# WZ4827R043-ESP32-V1_1-20230322.net
KiCad netlist of a schematic drawn in EAGLE
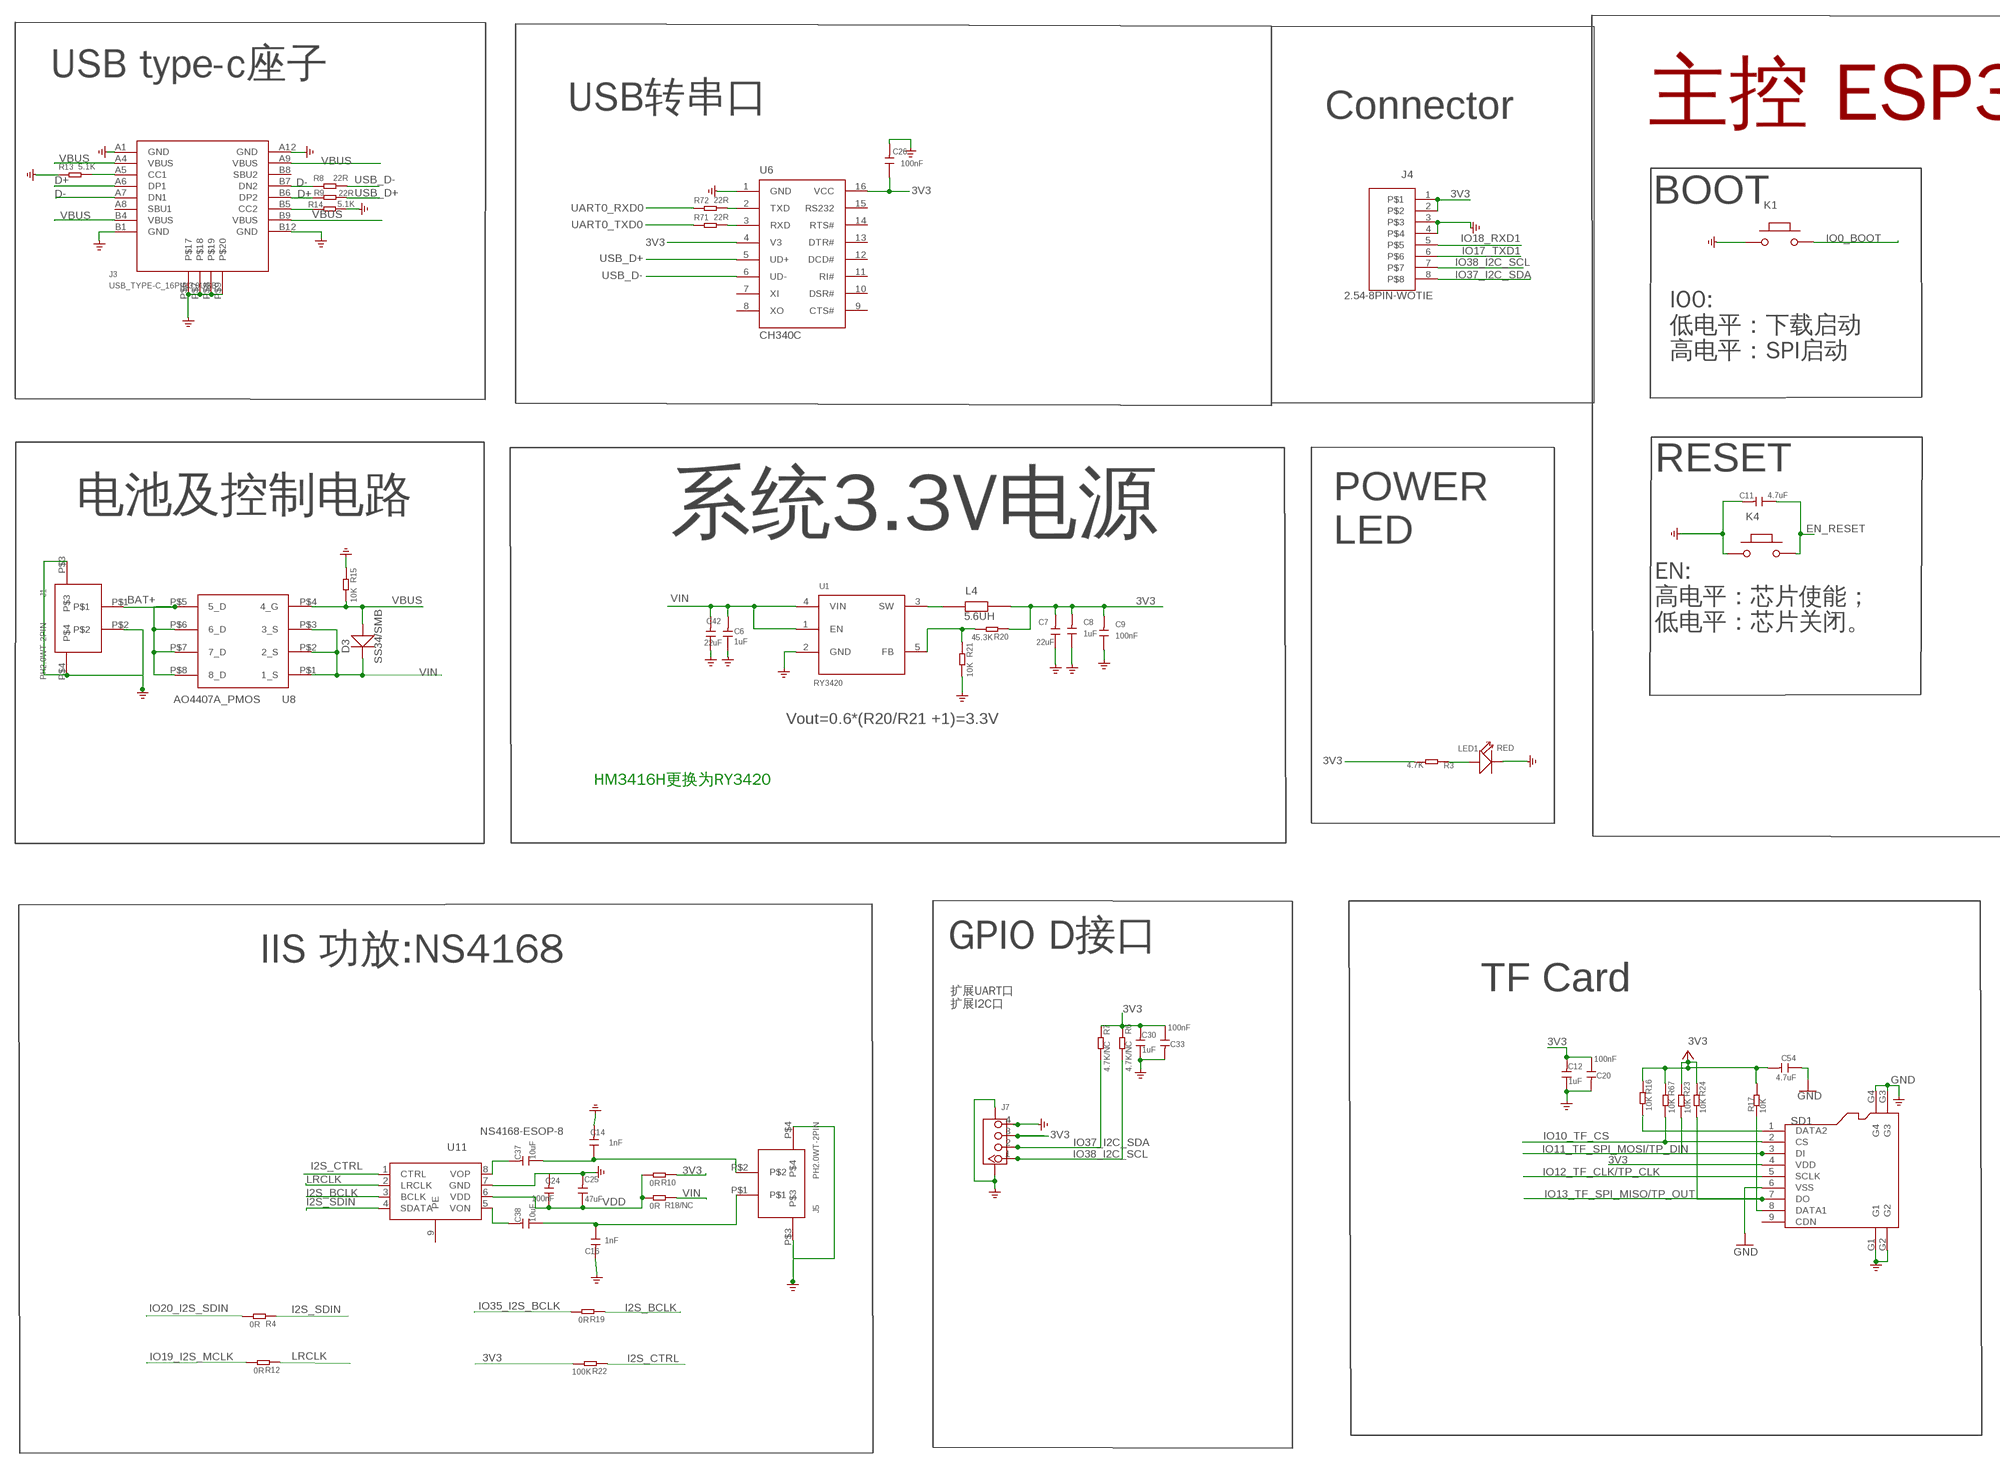
[diagram p0: schematic, sheet 1, part 1 of 2]
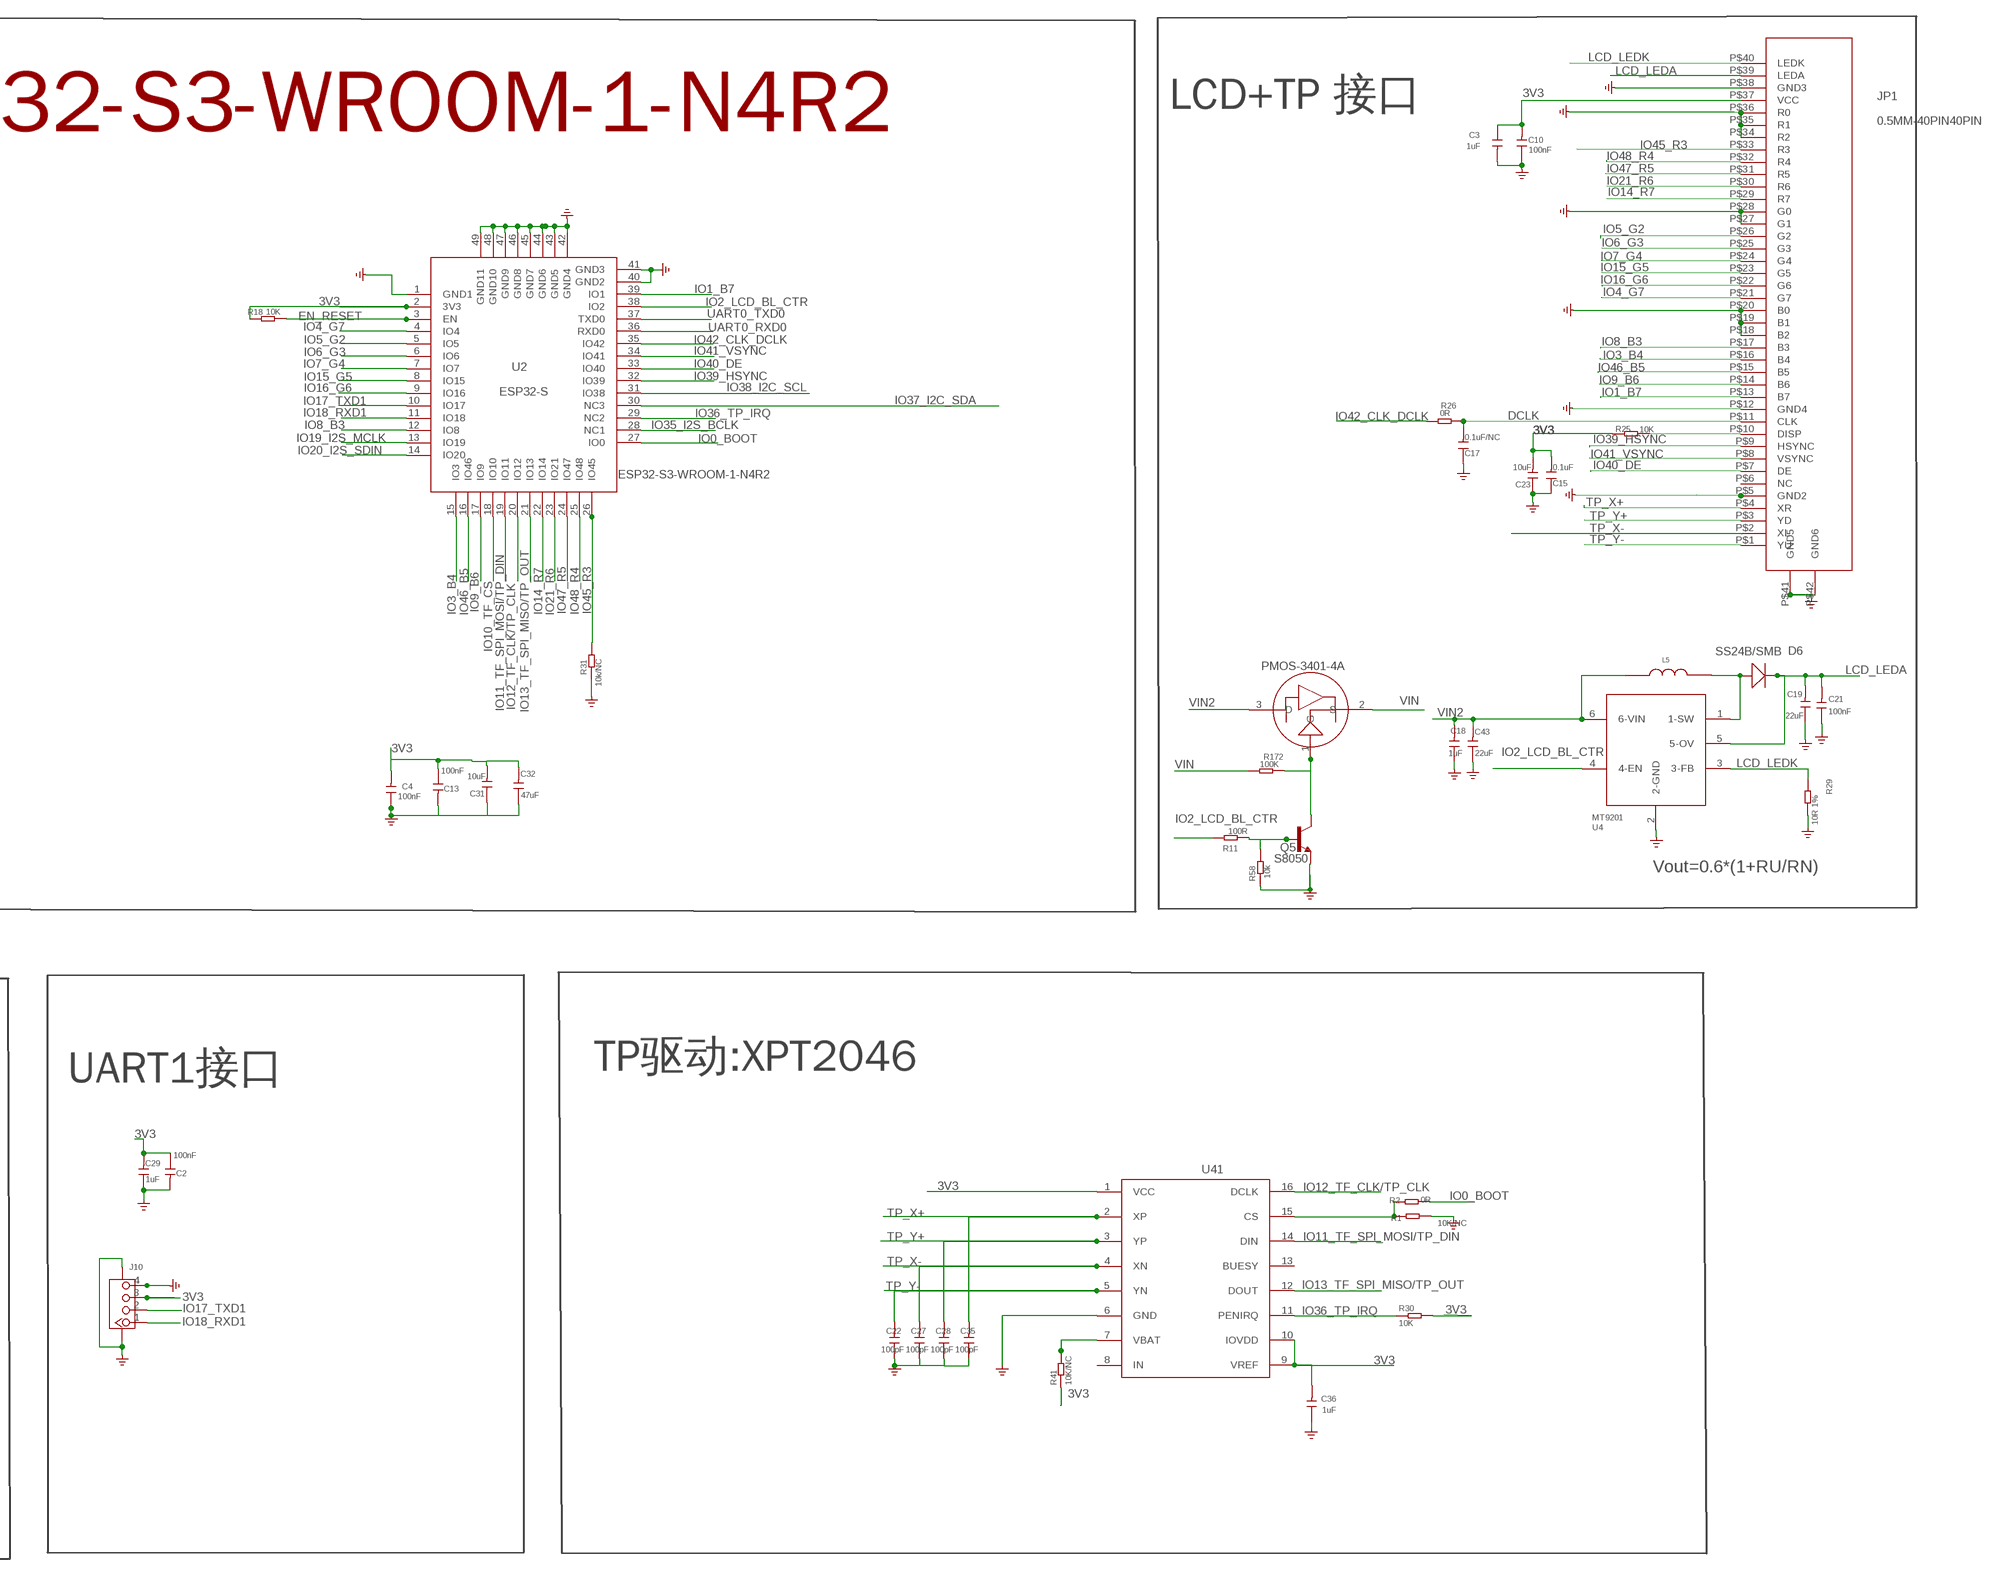
[diagram p1: schematic, sheet 1, part 2 of 2]

(export (version "E")
  (design (tool "Eeschema 10.0.6"))
  (components
    (comp (ref "C2")
      (value "100nF")
      (footprint "eagle-import:C0603")
      (libsource (lib "eagle-import") (part "C-0603"))
    )
    (comp (ref "C3")
      (value "1uF")
      (footprint "eagle-import:C0603")
      (libsource (lib "eagle-import") (part "C-0603"))
    )
    (comp (ref "C4")
      (value "100nF")
      (footprint "eagle-import:C0603")
      (libsource (lib "eagle-import") (part "C-0603"))
    )
    (comp (ref "C6")
      (value "1uF")
      (footprint "eagle-import:0603")
      (libsource (lib "eagle-import") (part "C0603"))
    )
    (comp (ref "C7")
      (value "22uF")
      (footprint "eagle-import:0805")
      (libsource (lib "eagle-import") (part "C0805"))
    )
    (comp (ref "C8")
      (value "1uF")
      (footprint "eagle-import:0603")
      (libsource (lib "eagle-import") (part "C0603"))
    )
    (comp (ref "C9")
      (value "100nF")
      (footprint "eagle-import:0603")
      (libsource (lib "eagle-import") (part "C0603"))
    )
    (comp (ref "C10")
      (value "100nF")
      (footprint "eagle-import:C0603")
      (libsource (lib "eagle-import") (part "C-0603"))
    )
    (comp (ref "C11")
      (value "4.7uF")
      (footprint "eagle-import:0603")
      (libsource (lib "eagle-import") (part "C0603"))
    )
    (comp (ref "C12")
      (value "1uF")
      (footprint "eagle-import:DISCRETE_C0603")
      (libsource (lib "eagle-import") (part "A_xbj_DISCRETE_C-0603"))
    )
    (comp (ref "C13")
      (value "100nF")
      (footprint "eagle-import:C0603")
      (libsource (lib "eagle-import") (part "C-0603"))
    )
    (comp (ref "C14")
      (value "1nF")
      (footprint "eagle-import:C0603")
      (libsource (lib "eagle-import") (part "C-0603"))
    )
    (comp (ref "C15")
      (value "0.1uF")
      (footprint "eagle-import:DISCRETE_C0603")
      (libsource (lib "eagle-import") (part "DISCRETE_C-0603"))
    )
    (comp (ref "C16")
      (value "1nF")
      (footprint "eagle-import:C0603")
      (libsource (lib "eagle-import") (part "C-0603"))
    )
    (comp (ref "C17")
      (value "0.1uF/NC")
      (footprint "eagle-import:DISCRETE_C0603")
      (libsource (lib "eagle-import") (part "DISCRETE_C-0603"))
    )
    (comp (ref "C18")
      (value "1uF")
      (footprint "eagle-import:0603")
      (libsource (lib "eagle-import") (part "C0603"))
    )
    (comp (ref "C19")
      (value "22uF")
      (footprint "eagle-import:0805")
      (libsource (lib "eagle-import") (part "C0805"))
    )
    (comp (ref "C20")
      (value "100nF")
      (footprint "eagle-import:C0603")
      (libsource (lib "eagle-import") (part "C-0603"))
    )
    (comp (ref "C21")
      (value "100nF")
      (footprint "eagle-import:0603")
      (libsource (lib "eagle-import") (part "C0603"))
    )
    (comp (ref "C22")
      (value "100pF")
      (footprint "eagle-import:0603")
      (libsource (lib "eagle-import") (part "C0603"))
    )
    (comp (ref "C23")
      (value "10uF")
      (footprint "eagle-import:DISCRETE_C0603")
      (libsource (lib "eagle-import") (part "DISCRETE_C-0603"))
    )
    (comp (ref "C24")
      (value "100nF")
      (footprint "eagle-import:C0603")
      (libsource (lib "eagle-import") (part "C-0603"))
    )
    (comp (ref "C25")
      (value "47uF")
      (footprint "eagle-import:0805")
      (libsource (lib "eagle-import") (part "C0805"))
    )
    (comp (ref "C26")
      (value "100nF")
      (footprint "eagle-import:0603")
      (libsource (lib "eagle-import") (part "C0603"))
    )
    (comp (ref "C27")
      (value "100pF")
      (footprint "eagle-import:0603")
      (libsource (lib "eagle-import") (part "C0603"))
    )
    (comp (ref "C28")
      (value "100pF")
      (footprint "eagle-import:0603")
      (libsource (lib "eagle-import") (part "C0603"))
    )
    (comp (ref "C29")
      (value "1uF")
      (footprint "eagle-import:DISCRETE_C0603")
      (libsource (lib "eagle-import") (part "A_xbj_DISCRETE_C-0603"))
    )
    (comp (ref "C30")
      (value "1uF")
      (footprint "eagle-import:DISCRETE_C0603")
      (libsource (lib "eagle-import") (part "A_xbj_DISCRETE_C-0603"))
    )
    (comp (ref "C31")
      (value "10uF")
      (footprint "eagle-import:DISCRETE_C0603")
      (libsource (lib "eagle-import") (part "DISCRETE_C-0603"))
    )
    (comp (ref "C32")
      (value "47uF")
      (footprint "eagle-import:0805")
      (libsource (lib "eagle-import") (part "C0805"))
    )
    (comp (ref "C33")
      (value "100nF")
      (footprint "eagle-import:C0603")
      (libsource (lib "eagle-import") (part "C-0603"))
    )
    (comp (ref "C35")
      (value "100pF")
      (footprint "eagle-import:0603")
      (libsource (lib "eagle-import") (part "C0603"))
    )
    (comp (ref "C36")
      (value "1uF")
      (footprint "eagle-import:DISCRETE_C0603")
      (libsource (lib "eagle-import") (part "A_xbj_DISCRETE_C-0603"))
    )
    (comp (ref "C37")
      (value "10uF")
      (footprint "eagle-import:DISCRETE_C0603")
      (libsource (lib "eagle-import") (part "A_xbj_DISCRETE_C-0603"))
    )
    (comp (ref "C38")
      (value "10uF")
      (footprint "eagle-import:DISCRETE_C0603")
      (libsource (lib "eagle-import") (part "A_xbj_DISCRETE_C-0603"))
    )
    (comp (ref "C42")
      (value "22uF")
      (footprint "eagle-import:0805")
      (libsource (lib "eagle-import") (part "C0805"))
    )
    (comp (ref "C43")
      (value "22uF")
      (footprint "eagle-import:0805")
      (libsource (lib "eagle-import") (part "C0805"))
    )
    (comp (ref "C54")
      (value "4.7uF")
      (footprint "eagle-import:DISCRETE_C0603")
      (libsource (lib "eagle-import") (part "DISCRETE_C-0603"))
    )
    (comp (ref "D3")
      (value "SS34/SMB")
      (footprint "eagle-import:214AB")
      (libsource (lib "eagle-import") (part "214ABDO-214AB"))
    )
    (comp (ref "D6")
      (value "SS24B/SMB")
      (footprint "eagle-import:214AB")
      (libsource (lib "eagle-import") (part "214ABDO-214AB"))
    )
    (comp (ref "J1")
      (value "PH2.0WT-2PIN")
      (footprint "eagle-import:PH2.0WT-2PIN")
      (libsource (lib "eagle-import") (part "PH2.0WT-2PIN"))
    )
    (comp (ref "J3")
      (value "USB_TYPE-C_16PIN3.0USB")
      (footprint "eagle-import:KEVIN_3.0TYPEC-SMD")
      (libsource (lib "eagle-import") (part "USB_TYPE-C_16PIN3.0USB"))
    )
    (comp (ref "J4")
      (value "2.54-8PIN-WOTIE")
      (footprint "eagle-import:2.54-8P-WOTIE")
      (libsource (lib "eagle-import") (part "2.54-8PIN-WOTIE"))
    )
    (comp (ref "J5")
      (value "PH2.0WT-2PIN")
      (footprint "eagle-import:PH2.0WT-2PIN")
      (libsource (lib "eagle-import") (part "PH2.0WT-2PIN"))
    )
    (comp (ref "J7")
      (value "CONNECTOR_TWIG-4P-2.0-SMD-FEMALE-REINFORCE90D")
      (footprint "eagle-import:CONNECTOR_4P-SMD-2.0-90D")
      (libsource (lib "eagle-import") (part "CONNECTOR_TWIG-4P-2.0-SMD-FEMALE-REINFORCE90D"))
    )
    (comp (ref "J10")
      (value "CONNECTOR_TWIG-4P-2.0-SMD-FEMALE-REINFORCE90D")
      (footprint "eagle-import:CONNECTOR_4P-SMD-2.0-90D")
      (libsource (lib "eagle-import") (part "CONNECTOR_TWIG-4P-2.0-SMD-FEMALE-REINFORCE90D"))
    )
    (comp (ref "JP1")
      (value "0.5MM-40PIN40PIN")
      (footprint "eagle-import:0.5MM_40P")
      (libsource (lib "eagle-import") (part "0.5MM-40PIN40PIN"))
    )
    (comp (ref "K1")
      (value "BUTTON")
      (footprint "eagle-import:157SW")
      (libsource (lib "eagle-import") (part "PB157"))
    )
    (comp (ref "K4")
      (value "BUTTON")
      (footprint "eagle-import:157SW")
      (libsource (lib "eagle-import") (part "PB157"))
    )
    (comp (ref "L4")
      (value "5.6UH")
      (footprint "eagle-import:CD54")
      (libsource (lib "eagle-import") (part "CROWPI2-MB-V1.4-20211012_CMP201209UD1R0MT"))
    )
    (comp (ref "L5")
      (value "CD32_6.8uH")
      (footprint "eagle-import:CD32")
      (libsource (lib "eagle-import") (part "CD32_950MA"))
    )
    (comp (ref "LED1")
      (value "RED")
      (footprint "eagle-import:DISCRETE_LED-0603")
      (libsource (lib "eagle-import") (part "DISCRETE_LED0603"))
    )
    (comp (ref "Q5")
      (value "S8050")
      (footprint "eagle-import:SPARKFUN_SOT23")
      (libsource (lib "eagle-import") (part "SPARKFUN_TRANSISTOR_NPNSOT23"))
    )
    (comp (ref "Q30")
      (value "PMOS-3401-4A")
      (footprint "eagle-import:SOT-23")
      (libsource (lib "eagle-import") (part "P-MOS-SOT23"))
    )
    (comp (ref "R1")
      (value "10K/NC")
      (footprint "eagle-import:R0603")
      (libsource (lib "eagle-import") (part "R0603"))
    )
    (comp (ref "R2")
      (value "0R")
      (footprint "eagle-import:DISCRETE_R0603")
      (libsource (lib "eagle-import") (part "Crowtail-_LED-V2.0-20190615-01_DISCRETE_R-0603"))
    )
    (comp (ref "R3")
      (value "4.7K")
      (footprint "eagle-import:DISCRETE_R0603")
      (libsource (lib "eagle-import") (part "Crowtail-_LED-V2.0-20190615-01_DISCRETE_R-0603"))
    )
    (comp (ref "R4")
      (value "0R")
      (footprint "eagle-import:DISCRETE_R0603")
      (libsource (lib "eagle-import") (part "Crowtail-_LED-V2.0-20190615-01_DISCRETE_R-0603"))
    )
    (comp (ref "R6")
      (value "4.7K/NC")
      (footprint "eagle-import:DISCRETE_R0603")
      (libsource (lib "eagle-import") (part "Crowtail-_LED-V2.0-20190615-01_DISCRETE_R-0603"))
    )
    (comp (ref "R7")
      (value "4.7K/NC")
      (footprint "eagle-import:DISCRETE_R0603")
      (libsource (lib "eagle-import") (part "Crowtail-_LED-V2.0-20190615-01_DISCRETE_R-0603"))
    )
    (comp (ref "R8")
      (value "22R")
      (footprint "eagle-import:DISCRETE_R0603")
      (libsource (lib "eagle-import") (part "Crowtail-_LED-V2.0-20190615-01_DISCRETE_R-0603"))
    )
    (comp (ref "R9")
      (value "22R")
      (footprint "eagle-import:DISCRETE_R0603")
      (libsource (lib "eagle-import") (part "Crowtail-_LED-V2.0-20190615-01_DISCRETE_R-0603"))
    )
    (comp (ref "R10")
      (value "0R")
      (footprint "eagle-import:DISCRETE_R0603")
      (libsource (lib "eagle-import") (part "Crowtail-_LED-V2.0-20190615-01_DISCRETE_R-0603"))
    )
    (comp (ref "R11")
      (value "100R")
      (footprint "eagle-import:R0603")
      (libsource (lib "eagle-import") (part "R0603"))
    )
    (comp (ref "R12")
      (value "0R")
      (footprint "eagle-import:DISCRETE_R0603")
      (libsource (lib "eagle-import") (part "Crowtail-_LED-V2.0-20190615-01_DISCRETE_R-0603"))
    )
    (comp (ref "R13")
      (value "5.1K")
      (footprint "eagle-import:DISCRETE_R0603")
      (libsource (lib "eagle-import") (part "Crowtail-_LED-V2.0-20190615-01_DISCRETE_R-0603"))
    )
    (comp (ref "R14")
      (value "5.1K")
      (footprint "eagle-import:DISCRETE_R0603")
      (libsource (lib "eagle-import") (part "Crowtail-_LED-V2.0-20190615-01_DISCRETE_R-0603"))
    )
    (comp (ref "R15")
      (value "10K")
      (footprint "eagle-import:DISCRETE_R0603")
      (libsource (lib "eagle-import") (part "Crowtail-_LED-V2.0-20190615-01_DISCRETE_R-0603"))
    )
    (comp (ref "R16")
      (value "10K")
      (footprint "eagle-import:DISCRETE_R0603")
      (libsource (lib "eagle-import") (part "Crowtail-_LED-V2.0-20190615-01_DISCRETE_R-0603"))
    )
    (comp (ref "R17")
      (value "10K")
      (footprint "eagle-import:DISCRETE_R0603")
      (libsource (lib "eagle-import") (part "Crowtail-_LED-V2.0-20190615-01_DISCRETE_R-0603"))
    )
    (comp (ref "R18")
      (value "10K")
      (footprint "eagle-import:DISCRETE_R0603")
      (libsource (lib "eagle-import") (part "Crowtail-_LED-V2.0-20190615-01_DISCRETE_R-0603"))
    )
    (comp (ref "R18/NC")
      (value "0R")
      (footprint "eagle-import:DISCRETE_R0603")
      (libsource (lib "eagle-import") (part "Crowtail-_LED-V2.0-20190615-01_DISCRETE_R-0603"))
    )
    (comp (ref "R19")
      (value "0R")
      (footprint "eagle-import:DISCRETE_R0603")
      (libsource (lib "eagle-import") (part "Crowtail-_LED-V2.0-20190615-01_DISCRETE_R-0603"))
    )
    (comp (ref "R20")
      (value "45.3K")
      (footprint "eagle-import:DISCRETE_R0603")
      (libsource (lib "eagle-import") (part "Crowtail-_LED-V2.0-20190615-01_DISCRETE_R-0603"))
    )
    (comp (ref "R21")
      (value "10K")
      (footprint "eagle-import:DISCRETE_R0603")
      (libsource (lib "eagle-import") (part "Crowtail-_LED-V2.0-20190615-01_DISCRETE_R-0603"))
    )
    (comp (ref "R22")
      (value "100K")
      (footprint "eagle-import:DISCRETE_R0603")
      (libsource (lib "eagle-import") (part "Crowtail-_LED-V2.0-20190615-01_DISCRETE_R-0603"))
    )
    (comp (ref "R23")
      (value "10K")
      (footprint "eagle-import:DISCRETE_R0603")
      (libsource (lib "eagle-import") (part "Crowtail-_LED-V2.0-20190615-01_DISCRETE_R-0603"))
    )
    (comp (ref "R24")
      (value "10K")
      (footprint "eagle-import:DISCRETE_R0603")
      (libsource (lib "eagle-import") (part "Crowtail-_LED-V2.0-20190615-01_DISCRETE_R-0603"))
    )
    (comp (ref "R25")
      (value "10K")
      (footprint "eagle-import:DISCRETE_R0603")
      (libsource (lib "eagle-import") (part "Crowtail-_LED-V2.0-20190615-01_DISCRETE_R-0603"))
    )
    (comp (ref "R26")
      (value "0R")
      (footprint "eagle-import:R0603")
      (libsource (lib "eagle-import") (part "R-0603"))
    )
    (comp (ref "R29")
      (value "10R 1%")
      (footprint "eagle-import:DISCRETE_R0603")
      (libsource (lib "eagle-import") (part "Crowtail-_LED-V2.0-20190615-01_DISCRETE_R-0603"))
    )
    (comp (ref "R30")
      (value "10K")
      (footprint "eagle-import:DISCRETE_R0603")
      (libsource (lib "eagle-import") (part "DISCRETE_R-0603"))
    )
    (comp (ref "R31")
      (value "10k/NC")
      (footprint "eagle-import:R0603")
      (libsource (lib "eagle-import") (part "R0603"))
    )
    (comp (ref "R41")
      (value "10K/NC")
      (footprint "eagle-import:DISCRETE_R0603")
      (libsource (lib "eagle-import") (part "DISCRETE_R-0603"))
    )
    (comp (ref "R58")
      (value "10k")
      (footprint "eagle-import:R0603")
      (libsource (lib "eagle-import") (part "R0603"))
    )
    (comp (ref "R67")
      (value "10K")
      (footprint "eagle-import:DISCRETE_R0603")
      (libsource (lib "eagle-import") (part "Crowtail-_LED-V2.0-20190615-01_DISCRETE_R-0603"))
    )
    (comp (ref "R71")
      (value "22R")
      (footprint "eagle-import:DISCRETE_R0603")
      (libsource (lib "eagle-import") (part "Crowtail-_LED-V2.0-20190615-01_DISCRETE_R-0603"))
    )
    (comp (ref "R72")
      (value "22R")
      (footprint "eagle-import:DISCRETE_R0603")
      (libsource (lib "eagle-import") (part "Crowtail-_LED-V2.0-20190615-01_DISCRETE_R-0603"))
    )
    (comp (ref "R172")
      (value "100K")
      (footprint "eagle-import:R0603")
      (libsource (lib "eagle-import") (part "R-0603"))
    )
    (comp (ref "SD1")
      (value "HOLDER-MICROSD-9P")
      (footprint "eagle-import:9P-SMD-W_-RING")
      (libsource (lib "eagle-import") (part "HOLDER-MICROSD-9P"))
    )
    (comp (ref "U1")
      (value "RY3420")
      (footprint "eagle-import:A_XBJ_SOT23-5")
      (libsource (lib "eagle-import") (part "A_XBJ_HM3420B"))
    )
    (comp (ref "U2")
      (value "ESP32-S")
      (footprint "eagle-import:ESP32-S3")
      (fields (field (name "U2") "ESP32-S3-WROOM-1-N4R2"))
      (libsource (lib "eagle-import") (part "ESP32-S"))
    )
    (comp (ref "U4")
      (value "MT9201")
      (footprint "eagle-import:SOT23-6")
      (libsource (lib "eagle-import") (part "MT9201"))
    )
    (comp (ref "U6")
      (value "CH340C")
      (footprint "eagle-import:SOP-16")
      (libsource (lib "eagle-import") (part "CH340G"))
    )
    (comp (ref "U8")
      (value "AO4407A_PMOS")
      (footprint "eagle-import:SOP8")
      (libsource (lib "eagle-import") (part "T_PMOS_AO4407A_SOP8"))
    )
    (comp (ref "U11")
      (value "NS4168-ESOP-8")
      (footprint "eagle-import:NS4168-ESOP-8")
      (libsource (lib "eagle-import") (part "NS4168-ESOP-8"))
    )
    (comp (ref "U41")
      (value "XPT2046")
      (footprint "eagle-import:XP2046-SSOP16")
      (libsource (lib "eagle-import") (part "XP2046"))
    )
  )
  (nets
    (net (code "1") (name "+3V3") (class "Default")
      (node (ref "C10") (pin "2") (pinfunction "2_2") (pintype "passive"))
      (node (ref "C12") (pin "2") (pinfunction "2_2") (pintype "passive"))
      (node (ref "C13") (pin "1") (pinfunction "1_1") (pintype "passive"))
      (node (ref "C15") (pin "2") (pinfunction "2_2") (pintype "passive"))
      (node (ref "C2") (pin "1") (pinfunction "1_1") (pintype "passive"))
      (node (ref "C20") (pin "1") (pinfunction "1_1") (pintype "passive"))
      (node (ref "C23") (pin "2") (pinfunction "2_2") (pintype "passive"))
      (node (ref "C26") (pin "1") (pinfunction "1_1") (pintype "passive"))
      (node (ref "C29") (pin "2") (pinfunction "2_2") (pintype "passive"))
      (node (ref "C3") (pin "1") (pinfunction "1_1") (pintype "passive"))
      (node (ref "C30") (pin "2") (pinfunction "2_2") (pintype "passive"))
      (node (ref "C31") (pin "2") (pinfunction "2_2") (pintype "passive"))
      (node (ref "C32") (pin "2") (pinfunction "2_2") (pintype "passive"))
      (node (ref "C33") (pin "1") (pinfunction "1_1") (pintype "passive"))
      (node (ref "C36") (pin "2") (pinfunction "2_2") (pintype "passive"))
      (node (ref "C4") (pin "2") (pinfunction "2_2") (pintype "passive"))
      (node (ref "C54") (pin "2") (pinfunction "2_2") (pintype "passive"))
      (node (ref "C7") (pin "2") (pinfunction "2_2") (pintype "passive"))
      (node (ref "C8") (pin "2") (pinfunction "2_2") (pintype "passive"))
      (node (ref "C9") (pin "2") (pinfunction "2_2") (pintype "passive"))
      (node (ref "J10") (pin "3") (pinfunction "3_3") (pintype "bidirectional"))
      (node (ref "J4") (pin "1") (pinfunction "P$1_1") (pintype "bidirectional"))
      (node (ref "J4") (pin "2") (pinfunction "P$2_2") (pintype "bidirectional"))
      (node (ref "J7") (pin "3") (pinfunction "3_3") (pintype "bidirectional"))
      (node (ref "JP1") (pin "P$37") (pinfunction "VCC_P$37") (pintype "bidirectional"))
      (node (ref "L4") (pin "2") (pinfunction "2_2") (pintype "bidirectional"))
      (node (ref "R10") (pin "1") (pinfunction "1_1") (pintype "passive"))
      (node (ref "R16") (pin "1") (pinfunction "1_1") (pintype "passive"))
      (node (ref "R17") (pin "1") (pinfunction "1_1") (pintype "passive"))
      (node (ref "R18") (pin "1") (pinfunction "1_1") (pintype "passive"))
      (node (ref "R20") (pin "1") (pinfunction "1_1") (pintype "passive"))
      (node (ref "R22") (pin "2") (pinfunction "2_2") (pintype "passive"))
      (node (ref "R23") (pin "1") (pinfunction "1_1") (pintype "passive"))
      (node (ref "R24") (pin "1") (pinfunction "1_1") (pintype "passive"))
      (node (ref "R25") (pin "1") (pinfunction "1_1") (pintype "passive"))
      (node (ref "R3") (pin "2") (pinfunction "2_2") (pintype "passive"))
      (node (ref "R30") (pin "2") (pinfunction "2_2") (pintype "passive"))
      (node (ref "R41") (pin "1") (pinfunction "1_1") (pintype "passive"))
      (node (ref "R6") (pin "1") (pinfunction "1_1") (pintype "passive"))
      (node (ref "R67") (pin "1") (pinfunction "1_1") (pintype "passive"))
      (node (ref "R7") (pin "1") (pinfunction "1_1") (pintype "passive"))
      (node (ref "SD1") (pin "4") (pinfunction "VDD_4") (pintype "bidirectional"))
      (node (ref "U2") (pin "2") (pinfunction "3V3_2") (pintype "bidirectional"))
      (node (ref "U41") (pin "1") (pinfunction "VCC_1") (pintype "bidirectional"))
      (node (ref "U41") (pin "10") (pinfunction "IOVDD_10") (pintype "bidirectional"))
      (node (ref "U41") (pin "9") (pinfunction "VREF_9") (pintype "bidirectional"))
      (node (ref "U6") (pin "16") (pinfunction "VCC_16") (pintype "bidirectional"))
      (node (ref "U6") (pin "4") (pinfunction "V3_4") (pintype "bidirectional"))
    )
    (net (code "2") (name "/BAT+") (class "Default")
      (node (ref "J1") (pin "P$1") (pinfunction "P$1_P$1") (pintype "bidirectional"))
      (node (ref "U8") (pin "P$5") (pinfunction "5_D_P$5") (pintype "bidirectional"))
      (node (ref "U8") (pin "P$6") (pinfunction "6_D_P$6") (pintype "bidirectional"))
      (node (ref "U8") (pin "P$7") (pinfunction "7_D_P$7") (pintype "bidirectional"))
      (node (ref "U8") (pin "P$8") (pinfunction "8_D_P$8") (pintype "bidirectional"))
    )
    (net (code "3") (name "/D+") (class "Default")
      (node (ref "J3") (pin "A6") (pinfunction "DP1_A6") (pintype "bidirectional"))
      (node (ref "J3") (pin "B6") (pinfunction "DP2_B6") (pintype "bidirectional"))
      (node (ref "R9") (pin "1") (pinfunction "1_1") (pintype "passive"))
    )
    (net (code "4") (name "/D-") (class "Default")
      (node (ref "J3") (pin "A7") (pinfunction "DN1_A7") (pintype "bidirectional"))
      (node (ref "J3") (pin "B7") (pinfunction "DN2_B7") (pintype "bidirectional"))
      (node (ref "R8") (pin "1") (pinfunction "1_1") (pintype "passive"))
    )
    (net (code "5") (name "/DCLK") (class "Default")
      (node (ref "C17") (pin "2") (pinfunction "2_2") (pintype "passive"))
      (node (ref "JP1") (pin "P$11") (pinfunction "CLK_P$11") (pintype "bidirectional"))
      (node (ref "R26") (pin "2") (pinfunction "2_2") (pintype "passive"))
    )
    (net (code "6") (name "/EN_RESET") (class "Default")
      (node (ref "C11") (pin "1") (pinfunction "1_1") (pintype "passive"))
      (node (ref "K4") (pin "2") (pinfunction "2_2") (pintype "passive"))
      (node (ref "R18") (pin "2") (pinfunction "2_2") (pintype "passive"))
      (node (ref "U2") (pin "3") (pinfunction "EN_3") (pintype "bidirectional"))
    )
    (net (code "7") (name "/I2S_BCLK") (class "Default")
      (node (ref "R19") (pin "1") (pinfunction "1_1") (pintype "passive"))
      (node (ref "U11") (pin "3") (pinfunction "BCLK_3") (pintype "bidirectional"))
    )
    (net (code "8") (name "/I2S_CTRL") (class "Default")
      (node (ref "R22") (pin "1") (pinfunction "1_1") (pintype "passive"))
      (node (ref "U11") (pin "1") (pinfunction "CTRL_1") (pintype "bidirectional"))
    )
    (net (code "9") (name "/I2S_SDIN") (class "Default")
      (node (ref "R4") (pin "1") (pinfunction "1_1") (pintype "passive"))
      (node (ref "U11") (pin "4") (pinfunction "SDATA_4") (pintype "bidirectional"))
    )
    (net (code "10") (name "/IO0_BOOT") (class "Default")
      (node (ref "K1") (pin "2") (pinfunction "2_2") (pintype "passive"))
      (node (ref "R2") (pin "1") (pinfunction "1_1") (pintype "passive"))
      (node (ref "U2") (pin "27") (pinfunction "IO0_27") (pintype "bidirectional"))
    )
    (net (code "11") (name "/IO1_B7") (class "Default")
      (node (ref "JP1") (pin "P$13") (pinfunction "B7_P$13") (pintype "bidirectional"))
      (node (ref "U2") (pin "39") (pinfunction "IO1_39") (pintype "bidirectional"))
    )
    (net (code "12") (name "/IO2_LCD_BL_CTR") (class "Default")
      (node (ref "R11") (pin "2") (pinfunction "2_2") (pintype "passive"))
      (node (ref "U2") (pin "38") (pinfunction "IO2_38") (pintype "bidirectional"))
      (node (ref "U4") (pin "4") (pinfunction "4-EN_4") (pintype "bidirectional"))
    )
    (net (code "13") (name "/IO3_B4") (class "Default")
      (node (ref "JP1") (pin "P$16") (pinfunction "B4_P$16") (pintype "bidirectional"))
      (node (ref "U2") (pin "15") (pinfunction "IO3_15") (pintype "bidirectional"))
    )
    (net (code "14") (name "/IO4_G7") (class "Default")
      (node (ref "JP1") (pin "P$21") (pinfunction "G7_P$21") (pintype "bidirectional"))
      (node (ref "U2") (pin "4") (pinfunction "IO4_4") (pintype "bidirectional"))
    )
    (net (code "15") (name "/IO5_G2") (class "Default")
      (node (ref "JP1") (pin "P$26") (pinfunction "G2_P$26") (pintype "bidirectional"))
      (node (ref "U2") (pin "5") (pinfunction "IO5_5") (pintype "bidirectional"))
    )
    (net (code "16") (name "/IO6_G3") (class "Default")
      (node (ref "JP1") (pin "P$25") (pinfunction "G3_P$25") (pintype "bidirectional"))
      (node (ref "U2") (pin "6") (pinfunction "IO6_6") (pintype "bidirectional"))
    )
    (net (code "17") (name "/IO7_G4") (class "Default")
      (node (ref "JP1") (pin "P$24") (pinfunction "G4_P$24") (pintype "bidirectional"))
      (node (ref "U2") (pin "7") (pinfunction "IO7_7") (pintype "bidirectional"))
    )
    (net (code "18") (name "/IO8_B3") (class "Default")
      (node (ref "JP1") (pin "P$17") (pinfunction "B3_P$17") (pintype "bidirectional"))
      (node (ref "U2") (pin "12") (pinfunction "IO8_12") (pintype "bidirectional"))
    )
    (net (code "19") (name "/IO9_B6") (class "Default")
      (node (ref "JP1") (pin "P$14") (pinfunction "B6_P$14") (pintype "bidirectional"))
      (node (ref "U2") (pin "17") (pinfunction "IO9_17") (pintype "bidirectional"))
    )
    (net (code "20") (name "/IO10_TF_CS") (class "Default")
      (node (ref "R67") (pin "2") (pinfunction "2_2") (pintype "passive"))
      (node (ref "SD1") (pin "2") (pinfunction "CS_2") (pintype "bidirectional"))
      (node (ref "U2") (pin "18") (pinfunction "IO10_18") (pintype "bidirectional"))
    )
    (net (code "21") (name "/IO11_TF_SPI_MOSI{slash}TP_DIN") (class "Default")
      (node (ref "R23") (pin "2") (pinfunction "2_2") (pintype "passive"))
      (node (ref "SD1") (pin "3") (pinfunction "DI_3") (pintype "bidirectional"))
      (node (ref "U2") (pin "19") (pinfunction "IO11_19") (pintype "bidirectional"))
      (node (ref "U41") (pin "14") (pinfunction "DIN_14") (pintype "bidirectional"))
    )
    (net (code "22") (name "/IO12_TF_CLK{slash}TP_CLK") (class "Default")
      (node (ref "SD1") (pin "5") (pinfunction "SCLK_5") (pintype "bidirectional"))
      (node (ref "U2") (pin "20") (pinfunction "IO12_20") (pintype "bidirectional"))
      (node (ref "U41") (pin "16") (pinfunction "DCLK_16") (pintype "bidirectional"))
    )
    (net (code "23") (name "/IO13_TF_SPI_MISO{slash}TP_OUT") (class "Default")
      (node (ref "R24") (pin "2") (pinfunction "2_2") (pintype "passive"))
      (node (ref "SD1") (pin "7") (pinfunction "DO_7") (pintype "bidirectional"))
      (node (ref "U2") (pin "21") (pinfunction "IO13_21") (pintype "bidirectional"))
      (node (ref "U41") (pin "12") (pinfunction "DOUT_12") (pintype "bidirectional"))
    )
    (net (code "24") (name "/IO14_R7") (class "Default")
      (node (ref "JP1") (pin "P$29") (pinfunction "R7_P$29") (pintype "bidirectional"))
      (node (ref "U2") (pin "22") (pinfunction "IO14_22") (pintype "bidirectional"))
    )
    (net (code "25") (name "/IO15_G5") (class "Default")
      (node (ref "JP1") (pin "P$23") (pinfunction "G5_P$23") (pintype "bidirectional"))
      (node (ref "U2") (pin "8") (pinfunction "IO15_8") (pintype "bidirectional"))
    )
    (net (code "26") (name "/IO16_G6") (class "Default")
      (node (ref "JP1") (pin "P$22") (pinfunction "G6_P$22") (pintype "bidirectional"))
      (node (ref "U2") (pin "9") (pinfunction "IO16_9") (pintype "bidirectional"))
    )
    (net (code "27") (name "/IO17_TXD1") (class "Default")
      (node (ref "J10") (pin "2") (pinfunction "2_2") (pintype "bidirectional"))
      (node (ref "J4") (pin "6") (pinfunction "P$6_6") (pintype "bidirectional"))
      (node (ref "U2") (pin "10") (pinfunction "IO17_10") (pintype "bidirectional"))
    )
    (net (code "28") (name "/IO18_RXD1") (class "Default")
      (node (ref "J10") (pin "1") (pinfunction "1_1") (pintype "bidirectional"))
      (node (ref "J4") (pin "5") (pinfunction "P$5_5") (pintype "bidirectional"))
      (node (ref "U2") (pin "11") (pinfunction "IO18_11") (pintype "bidirectional"))
    )
    (net (code "29") (name "/IO19_I2S_MCLK") (class "Default")
      (node (ref "R12") (pin "2") (pinfunction "2_2") (pintype "passive"))
      (node (ref "U2") (pin "13") (pinfunction "IO19_13") (pintype "bidirectional"))
    )
    (net (code "30") (name "/IO20_I2S_SDIN") (class "Default")
      (node (ref "R4") (pin "2") (pinfunction "2_2") (pintype "passive"))
      (node (ref "U2") (pin "14") (pinfunction "IO20_14") (pintype "bidirectional"))
    )
    (net (code "31") (name "/IO21_R6") (class "Default")
      (node (ref "JP1") (pin "P$30") (pinfunction "R6_P$30") (pintype "bidirectional"))
      (node (ref "U2") (pin "23") (pinfunction "IO21_23") (pintype "bidirectional"))
    )
    (net (code "32") (name "/IO35_I2S_BCLK") (class "Default")
      (node (ref "R19") (pin "2") (pinfunction "2_2") (pintype "passive"))
      (node (ref "U2") (pin "28") (pinfunction "NC1_28") (pintype "bidirectional"))
    )
    (net (code "33") (name "/IO36_TP_IRQ") (class "Default")
      (node (ref "R30") (pin "1") (pinfunction "1_1") (pintype "passive"))
      (node (ref "U2") (pin "29") (pinfunction "NC2_29") (pintype "bidirectional"))
      (node (ref "U41") (pin "11") (pinfunction "PENIRQ_11") (pintype "bidirectional"))
    )
    (net (code "34") (name "/IO37_I2C_SDA") (class "Default")
      (node (ref "J4") (pin "8") (pinfunction "P$8_8") (pintype "bidirectional"))
      (node (ref "J7") (pin "2") (pinfunction "2_2") (pintype "bidirectional"))
      (node (ref "R7") (pin "2") (pinfunction "2_2") (pintype "passive"))
      (node (ref "U2") (pin "30") (pinfunction "NC3_30") (pintype "bidirectional"))
    )
    (net (code "35") (name "/IO38_I2C_SCL") (class "Default")
      (node (ref "J4") (pin "7") (pinfunction "P$7_7") (pintype "bidirectional"))
      (node (ref "J7") (pin "1") (pinfunction "1_1") (pintype "bidirectional"))
      (node (ref "R6") (pin "2") (pinfunction "2_2") (pintype "passive"))
      (node (ref "U2") (pin "31") (pinfunction "IO38_31") (pintype "bidirectional"))
    )
    (net (code "36") (name "/IO39_HSYNC") (class "Default")
      (node (ref "JP1") (pin "P$9") (pinfunction "HSYNC_P$9") (pintype "bidirectional"))
      (node (ref "U2") (pin "32") (pinfunction "IO39_32") (pintype "bidirectional"))
    )
    (net (code "37") (name "/IO40_DE") (class "Default")
      (node (ref "JP1") (pin "P$7") (pinfunction "DE_P$7") (pintype "bidirectional"))
      (node (ref "U2") (pin "33") (pinfunction "IO40_33") (pintype "bidirectional"))
    )
    (net (code "38") (name "/IO41_VSYNC") (class "Default")
      (node (ref "JP1") (pin "P$8") (pinfunction "VSYNC_P$8") (pintype "bidirectional"))
      (node (ref "U2") (pin "34") (pinfunction "IO41_34") (pintype "bidirectional"))
    )
    (net (code "39") (name "/IO42_CLK_DCLK") (class "Default")
      (node (ref "R26") (pin "1") (pinfunction "1_1") (pintype "passive"))
      (node (ref "U2") (pin "35") (pinfunction "IO42_35") (pintype "bidirectional"))
    )
    (net (code "40") (name "/IO45_R3") (class "Default")
      (node (ref "JP1") (pin "P$33") (pinfunction "R3_P$33") (pintype "bidirectional"))
      (node (ref "R31") (pin "2") (pinfunction "2_2") (pintype "passive"))
      (node (ref "U2") (pin "26") (pinfunction "IO45_26") (pintype "bidirectional"))
    )
    (net (code "41") (name "/IO46_B5") (class "Default")
      (node (ref "JP1") (pin "P$15") (pinfunction "B5_P$15") (pintype "bidirectional"))
      (node (ref "U2") (pin "16") (pinfunction "IO46_16") (pintype "bidirectional"))
    )
    (net (code "42") (name "/IO47_R5") (class "Default")
      (node (ref "JP1") (pin "P$31") (pinfunction "R5_P$31") (pintype "bidirectional"))
      (node (ref "U2") (pin "24") (pinfunction "IO47_24") (pintype "bidirectional"))
    )
    (net (code "43") (name "/IO48_R4") (class "Default")
      (node (ref "JP1") (pin "P$32") (pinfunction "R4_P$32") (pintype "bidirectional"))
      (node (ref "U2") (pin "25") (pinfunction "IO48_25") (pintype "bidirectional"))
    )
    (net (code "44") (name "/LCD_LEDA") (class "Default")
      (node (ref "C19") (pin "2") (pinfunction "2_2") (pintype "passive"))
      (node (ref "C21") (pin "2") (pinfunction "2_2") (pintype "passive"))
      (node (ref "D6") (pin "2") (pinfunction "-_2") (pintype "passive"))
      (node (ref "JP1") (pin "P$39") (pinfunction "LEDA_P$39") (pintype "bidirectional"))
      (node (ref "U4") (pin "5") (pinfunction "5-OV_5") (pintype "bidirectional"))
    )
    (net (code "45") (name "/LCD_LEDK") (class "Default")
      (node (ref "JP1") (pin "P$40") (pinfunction "LEDK_P$40") (pintype "bidirectional"))
      (node (ref "R29") (pin "1") (pinfunction "1_1") (pintype "passive"))
      (node (ref "U4") (pin "3") (pinfunction "3-FB_3") (pintype "bidirectional"))
    )
    (net (code "46") (name "/LRCLK") (class "Default")
      (node (ref "R12") (pin "1") (pinfunction "1_1") (pintype "passive"))
      (node (ref "U11") (pin "2") (pinfunction "LRCLK_2") (pintype "bidirectional"))
    )
    (net (code "47") (name "/TP_X+") (class "Default")
      (node (ref "C35") (pin "2") (pinfunction "2_2") (pintype "passive"))
      (node (ref "JP1") (pin "P$4") (pinfunction "XR_P$4") (pintype "bidirectional"))
      (node (ref "U41") (pin "2") (pinfunction "XP_2") (pintype "bidirectional"))
    )
    (net (code "48") (name "/TP_X-") (class "Default")
      (node (ref "C27") (pin "2") (pinfunction "2_2") (pintype "passive"))
      (node (ref "JP1") (pin "P$2") (pinfunction "XL_P$2") (pintype "bidirectional"))
      (node (ref "U41") (pin "4") (pinfunction "XN_4") (pintype "bidirectional"))
    )
    (net (code "49") (name "/TP_Y+") (class "Default")
      (node (ref "C28") (pin "2") (pinfunction "2_2") (pintype "passive"))
      (node (ref "JP1") (pin "P$3") (pinfunction "YD_P$3") (pintype "bidirectional"))
      (node (ref "U41") (pin "3") (pinfunction "YP_3") (pintype "bidirectional"))
    )
    (net (code "50") (name "/TP_Y-") (class "Default")
      (node (ref "C22") (pin "2") (pinfunction "2_2") (pintype "passive"))
      (node (ref "JP1") (pin "P$1") (pinfunction "YU_P$1") (pintype "bidirectional"))
      (node (ref "U41") (pin "5") (pinfunction "YN_5") (pintype "bidirectional"))
    )
    (net (code "51") (name "/UART0_RXD0") (class "Default")
      (node (ref "R72") (pin "1") (pinfunction "1_1") (pintype "passive"))
      (node (ref "U2") (pin "36") (pinfunction "RXD0_36") (pintype "bidirectional"))
    )
    (net (code "52") (name "/UART0_TXD0") (class "Default")
      (node (ref "R71") (pin "1") (pinfunction "1_1") (pintype "passive"))
      (node (ref "U2") (pin "37") (pinfunction "TXD0_37") (pintype "bidirectional"))
    )
    (net (code "53") (name "/USB_D+") (class "Default")
      (node (ref "R9") (pin "2") (pinfunction "2_2") (pintype "passive"))
      (node (ref "U6") (pin "5") (pinfunction "UD+_5") (pintype "bidirectional"))
    )
    (net (code "54") (name "/USB_D-") (class "Default")
      (node (ref "R8") (pin "2") (pinfunction "2_2") (pintype "passive"))
      (node (ref "U6") (pin "6") (pinfunction "UD-_6") (pintype "bidirectional"))
    )
    (net (code "55") (name "/VBUS") (class "Default")
      (node (ref "D3") (pin "1") (pinfunction "+_1") (pintype "passive"))
      (node (ref "J3") (pin "A4") (pinfunction "VBUS_A4") (pintype "bidirectional"))
      (node (ref "J3") (pin "A9") (pinfunction "VBUS_A9") (pintype "bidirectional"))
      (node (ref "J3") (pin "B4") (pinfunction "VBUS_B4") (pintype "bidirectional"))
      (node (ref "J3") (pin "B9") (pinfunction "VBUS_B9") (pintype "bidirectional"))
      (node (ref "R15") (pin "2") (pinfunction "2_2") (pintype "passive"))
      (node (ref "U8") (pin "P$4") (pinfunction "4_G_P$4") (pintype "bidirectional"))
    )
    (net (code "56") (name "/VDD") (class "Default")
      (node (ref "C24") (pin "1") (pinfunction "1_1") (pintype "passive"))
      (node (ref "C25") (pin "1") (pinfunction "1_1") (pintype "passive"))
      (node (ref "R10") (pin "2") (pinfunction "2_2") (pintype "passive"))
      (node (ref "R18/NC") (pin "2") (pinfunction "2_2") (pintype "passive"))
      (node (ref "U11") (pin "6") (pinfunction "VDD_6") (pintype "bidirectional"))
    )
    (net (code "57") (name "/VIN") (class "Default")
      (node (ref "C42") (pin "2") (pinfunction "2_2") (pintype "passive"))
      (node (ref "C6") (pin "2") (pinfunction "2_2") (pintype "passive"))
      (node (ref "D3") (pin "2") (pinfunction "-_2") (pintype "passive"))
      (node (ref "Q30") (pin "2") (pinfunction "S_2") (pintype "bidirectional"))
      (node (ref "R172") (pin "1") (pinfunction "1_1") (pintype "passive"))
      (node (ref "R18/NC") (pin "1") (pinfunction "1_1") (pintype "passive"))
      (node (ref "U1") (pin "1") (pinfunction "EN_1") (pintype "bidirectional"))
      (node (ref "U1") (pin "4") (pinfunction "VIN_4") (pintype "bidirectional"))
      (node (ref "U8") (pin "P$1") (pinfunction "1_S_P$1") (pintype "bidirectional"))
      (node (ref "U8") (pin "P$2") (pinfunction "2_S_P$2") (pintype "bidirectional"))
      (node (ref "U8") (pin "P$3") (pinfunction "3_S_P$3") (pintype "bidirectional"))
    )
    (net (code "58") (name "/VIN2") (class "Default")
      (node (ref "C18") (pin "2") (pinfunction "2_2") (pintype "passive"))
      (node (ref "C43") (pin "2") (pinfunction "2_2") (pintype "passive"))
      (node (ref "L5") (pin "1") (pinfunction "1_1") (pintype "bidirectional"))
      (node (ref "Q30") (pin "3") (pinfunction "D_3") (pintype "bidirectional"))
      (node (ref "U4") (pin "6") (pinfunction "6-VIN_6") (pintype "bidirectional"))
    )
    (net (code "59") (name "GND") (class "Default")
      (node (ref "C10") (pin "1") (pinfunction "1_1") (pintype "passive"))
      (node (ref "C11") (pin "2") (pinfunction "2_2") (pintype "passive"))
      (node (ref "C12") (pin "1") (pinfunction "1_1") (pintype "passive"))
      (node (ref "C13") (pin "2") (pinfunction "2_2") (pintype "passive"))
      (node (ref "C14") (pin "2") (pinfunction "2_2") (pintype "passive"))
      (node (ref "C15") (pin "1") (pinfunction "1_1") (pintype "passive"))
      (node (ref "C16") (pin "2") (pinfunction "2_2") (pintype "passive"))
      (node (ref "C17") (pin "1") (pinfunction "1_1") (pintype "passive"))
      (node (ref "C18") (pin "1") (pinfunction "1_1") (pintype "passive"))
      (node (ref "C19") (pin "1") (pinfunction "1_1") (pintype "passive"))
      (node (ref "C2") (pin "2") (pinfunction "2_2") (pintype "passive"))
      (node (ref "C20") (pin "2") (pinfunction "2_2") (pintype "passive"))
      (node (ref "C21") (pin "1") (pinfunction "1_1") (pintype "passive"))
      (node (ref "C22") (pin "1") (pinfunction "1_1") (pintype "passive"))
      (node (ref "C23") (pin "1") (pinfunction "1_1") (pintype "passive"))
      (node (ref "C24") (pin "2") (pinfunction "2_2") (pintype "passive"))
      (node (ref "C25") (pin "2") (pinfunction "2_2") (pintype "passive"))
      (node (ref "C26") (pin "2") (pinfunction "2_2") (pintype "passive"))
      (node (ref "C27") (pin "1") (pinfunction "1_1") (pintype "passive"))
      (node (ref "C28") (pin "1") (pinfunction "1_1") (pintype "passive"))
      (node (ref "C29") (pin "1") (pinfunction "1_1") (pintype "passive"))
      (node (ref "C3") (pin "2") (pinfunction "2_2") (pintype "passive"))
      (node (ref "C30") (pin "1") (pinfunction "1_1") (pintype "passive"))
      (node (ref "C31") (pin "1") (pinfunction "1_1") (pintype "passive"))
      (node (ref "C32") (pin "1") (pinfunction "1_1") (pintype "passive"))
      (node (ref "C33") (pin "2") (pinfunction "2_2") (pintype "passive"))
      (node (ref "C35") (pin "1") (pinfunction "1_1") (pintype "passive"))
      (node (ref "C36") (pin "1") (pinfunction "1_1") (pintype "passive"))
      (node (ref "C4") (pin "1") (pinfunction "1_1") (pintype "passive"))
      (node (ref "C42") (pin "1") (pinfunction "1_1") (pintype "passive"))
      (node (ref "C43") (pin "1") (pinfunction "1_1") (pintype "passive"))
      (node (ref "C54") (pin "1") (pinfunction "1_1") (pintype "passive"))
      (node (ref "C6") (pin "1") (pinfunction "1_1") (pintype "passive"))
      (node (ref "C7") (pin "1") (pinfunction "1_1") (pintype "passive"))
      (node (ref "C8") (pin "1") (pinfunction "1_1") (pintype "passive"))
      (node (ref "C9") (pin "1") (pinfunction "1_1") (pintype "passive"))
      (node (ref "J1") (pin "P$2") (pinfunction "P$2_P$2") (pintype "bidirectional"))
      (node (ref "J1") (pin "P$3") (pinfunction "P$3_P$3") (pintype "bidirectional"))
      (node (ref "J1") (pin "P$4") (pinfunction "P$4_P$4") (pintype "bidirectional"))
      (node (ref "J10") (pin "4") (pinfunction "4_4") (pintype "bidirectional"))
      (node (ref "J10") (pin "SS1") (pinfunction "SS1_SS1") (pintype "bidirectional"))
      (node (ref "J10") (pin "SS2") (pinfunction "SS2_SS2") (pintype "bidirectional"))
      (node (ref "J3") (pin "A1") (pinfunction "GND_A1") (pintype "bidirectional"))
      (node (ref "J3") (pin "A12") (pinfunction "GND_A12") (pintype "bidirectional"))
      (node (ref "J3") (pin "B1") (pinfunction "GND_B1") (pintype "bidirectional"))
      (node (ref "J3") (pin "B12") (pinfunction "GND_B12") (pintype "bidirectional"))
      (node (ref "J3") (pin "P$6") (pinfunction "P$17_P$6") (pintype "bidirectional"))
      (node (ref "J3") (pin "P$7") (pinfunction "P$18_P$7") (pintype "bidirectional"))
      (node (ref "J3") (pin "P$8") (pinfunction "P$19_P$8") (pintype "bidirectional"))
      (node (ref "J3") (pin "P$9") (pinfunction "P$20_P$9") (pintype "bidirectional"))
      (node (ref "J4") (pin "3") (pinfunction "P$3_3") (pintype "bidirectional"))
      (node (ref "J4") (pin "4") (pinfunction "P$4_4") (pintype "bidirectional"))
      (node (ref "J5") (pin "P$3") (pinfunction "P$3_P$3") (pintype "bidirectional"))
      (node (ref "J5") (pin "P$4") (pinfunction "P$4_P$4") (pintype "bidirectional"))
      (node (ref "J7") (pin "4") (pinfunction "4_4") (pintype "bidirectional"))
      (node (ref "J7") (pin "SS1") (pinfunction "SS1_SS1") (pintype "bidirectional"))
      (node (ref "J7") (pin "SS2") (pinfunction "SS2_SS2") (pintype "bidirectional"))
      (node (ref "JP1") (pin "P$12") (pinfunction "GND4_P$12") (pintype "bidirectional"))
      (node (ref "JP1") (pin "P$18") (pinfunction "B2_P$18") (pintype "bidirectional"))
      (node (ref "JP1") (pin "P$19") (pinfunction "B1_P$19") (pintype "bidirectional"))
      (node (ref "JP1") (pin "P$20") (pinfunction "B0_P$20") (pintype "bidirectional"))
      (node (ref "JP1") (pin "P$27") (pinfunction "G1_P$27") (pintype "bidirectional"))
      (node (ref "JP1") (pin "P$28") (pinfunction "G0_P$28") (pintype "bidirectional"))
      (node (ref "JP1") (pin "P$34") (pinfunction "R2_P$34") (pintype "bidirectional"))
      (node (ref "JP1") (pin "P$35") (pinfunction "R1_P$35") (pintype "bidirectional"))
      (node (ref "JP1") (pin "P$36") (pinfunction "R0_P$36") (pintype "bidirectional"))
      (node (ref "JP1") (pin "P$38") (pinfunction "GND3_P$38") (pintype "bidirectional"))
      (node (ref "JP1") (pin "P$41") (pinfunction "GND5_P$41") (pintype "bidirectional"))
      (node (ref "JP1") (pin "P$42") (pinfunction "GND6_P$42") (pintype "bidirectional"))
      (node (ref "JP1") (pin "P$5") (pinfunction "GND2_P$5") (pintype "bidirectional"))
      (node (ref "K1") (pin "1") (pinfunction "1_1") (pintype "passive"))
      (node (ref "K4") (pin "1") (pinfunction "1_1") (pintype "passive"))
      (node (ref "LED1") (pin "-") (pinfunction "-_-") (pintype "passive"))
      (node (ref "Q5") (pin "2") (pinfunction "E_2") (pintype "passive"))
      (node (ref "R1") (pin "1") (pinfunction "1_1") (pintype "passive"))
      (node (ref "R13") (pin "1") (pinfunction "1_1") (pintype "passive"))
      (node (ref "R14") (pin "2") (pinfunction "2_2") (pintype "passive"))
      (node (ref "R15") (pin "1") (pinfunction "1_1") (pintype "passive"))
      (node (ref "R21") (pin "2") (pinfunction "2_2") (pintype "passive"))
      (node (ref "R29") (pin "2") (pinfunction "2_2") (pintype "passive"))
      (node (ref "R31") (pin "1") (pinfunction "1_1") (pintype "passive"))
      (node (ref "R58") (pin "1") (pinfunction "1_1") (pintype "passive"))
      (node (ref "SD1") (pin "6") (pinfunction "VSS_6") (pintype "bidirectional"))
      (node (ref "SD1") (pin "G1") (pinfunction "G1_G1") (pintype "bidirectional"))
      (node (ref "SD1") (pin "G2") (pinfunction "G2_G2") (pintype "bidirectional"))
      (node (ref "SD1") (pin "G3") (pinfunction "G3_G3") (pintype "bidirectional"))
      (node (ref "SD1") (pin "G4") (pinfunction "G4_G4") (pintype "bidirectional"))
      (node (ref "U1") (pin "2") (pinfunction "GND_2") (pintype "bidirectional"))
      (node (ref "U11") (pin "7") (pinfunction "GND_7") (pintype "bidirectional"))
      (node (ref "U2") (pin "1") (pinfunction "GND1_1") (pintype "bidirectional"))
      (node (ref "U2") (pin "40") (pinfunction "GND2_40") (pintype "bidirectional"))
      (node (ref "U2") (pin "41") (pinfunction "GND3_41") (pintype "bidirectional"))
      (node (ref "U2") (pin "42") (pinfunction "GND4_42") (pintype "bidirectional"))
      (node (ref "U2") (pin "43") (pinfunction "GND5_43") (pintype "bidirectional"))
      (node (ref "U2") (pin "44") (pinfunction "GND6_44") (pintype "bidirectional"))
      (node (ref "U2") (pin "45") (pinfunction "GND7_45") (pintype "bidirectional"))
      (node (ref "U2") (pin "46") (pinfunction "GND8_46") (pintype "bidirectional"))
      (node (ref "U2") (pin "47") (pinfunction "GND9_47") (pintype "bidirectional"))
      (node (ref "U2") (pin "48") (pinfunction "GND10_48") (pintype "bidirectional"))
      (node (ref "U2") (pin "49") (pinfunction "GND11_49") (pintype "bidirectional"))
      (node (ref "U4") (pin "2") (pinfunction "2-GND_2") (pintype "bidirectional"))
      (node (ref "U41") (pin "6") (pinfunction "GND_6") (pintype "bidirectional"))
      (node (ref "U6") (pin "1") (pinfunction "GND_1") (pintype "bidirectional"))
    )
    (net (code "60") (name "Net-(C14-Pad1)") (class "Default")
      (node (ref "C14") (pin "1") (pinfunction "1_1") (pintype "passive"))
      (node (ref "C37") (pin "1") (pinfunction "1_1") (pintype "passive"))
      (node (ref "J5") (pin "P$2") (pinfunction "P$2_P$2") (pintype "bidirectional"))
    )
    (net (code "61") (name "Net-(C16-Pad1)") (class "Default")
      (node (ref "C16") (pin "1") (pinfunction "1_1") (pintype "passive"))
      (node (ref "C38") (pin "1") (pinfunction "1_1") (pintype "passive"))
      (node (ref "J5") (pin "P$1") (pinfunction "P$1_P$1") (pintype "bidirectional"))
    )
    (net (code "62") (name "Net-(D6-+)") (class "Default")
      (node (ref "D6") (pin "1") (pinfunction "+_1") (pintype "passive"))
      (node (ref "L5") (pin "2") (pinfunction "2_2") (pintype "bidirectional"))
      (node (ref "U4") (pin "1") (pinfunction "1-SW_1") (pintype "bidirectional"))
    )
    (net (code "63") (name "Net-(J3-CC1)") (class "Default")
      (node (ref "J3") (pin "A5") (pinfunction "CC1_A5") (pintype "bidirectional"))
      (node (ref "R13") (pin "2") (pinfunction "2_2") (pintype "passive"))
    )
    (net (code "64") (name "Net-(J3-CC2)") (class "Default")
      (node (ref "J3") (pin "B5") (pinfunction "CC2_B5") (pintype "bidirectional"))
      (node (ref "R14") (pin "1") (pinfunction "1_1") (pintype "passive"))
    )
    (net (code "65") (name "Net-(JP1-DISP)") (class "Default")
      (node (ref "JP1") (pin "P$10") (pinfunction "DISP_P$10") (pintype "bidirectional"))
      (node (ref "R25") (pin "2") (pinfunction "2_2") (pintype "passive"))
    )
    (net (code "66") (name "Net-(LED1-Pad+)") (class "Default")
      (node (ref "LED1") (pin "+") (pinfunction "+_+") (pintype "passive"))
      (node (ref "R3") (pin "1") (pinfunction "1_1") (pintype "passive"))
    )
    (net (code "67") (name "Net-(Q5-B)") (class "Default")
      (node (ref "Q5") (pin "1") (pinfunction "B_1") (pintype "passive"))
      (node (ref "R11") (pin "1") (pinfunction "1_1") (pintype "passive"))
      (node (ref "R58") (pin "2") (pinfunction "2_2") (pintype "passive"))
    )
    (net (code "68") (name "Net-(Q30-G)") (class "Default")
      (node (ref "Q30") (pin "1") (pinfunction "G_1") (pintype "bidirectional"))
      (node (ref "Q5") (pin "3") (pinfunction "C_3") (pintype "passive"))
      (node (ref "R172") (pin "2") (pinfunction "2_2") (pintype "passive"))
    )
    (net (code "69") (name "Net-(SD1-DATA1)") (class "Default")
      (node (ref "R17") (pin "2") (pinfunction "2_2") (pintype "passive"))
      (node (ref "SD1") (pin "8") (pinfunction "DATA1_8") (pintype "bidirectional"))
    )
    (net (code "70") (name "Net-(SD1-DATA2)") (class "Default")
      (node (ref "R16") (pin "2") (pinfunction "2_2") (pintype "passive"))
      (node (ref "SD1") (pin "1") (pinfunction "DATA2_1") (pintype "bidirectional"))
    )
    (net (code "71") (name "Net-(U1-FB)") (class "Default")
      (node (ref "R20") (pin "2") (pinfunction "2_2") (pintype "passive"))
      (node (ref "R21") (pin "1") (pinfunction "1_1") (pintype "passive"))
      (node (ref "U1") (pin "5") (pinfunction "FB_5") (pintype "bidirectional"))
    )
    (net (code "72") (name "Net-(U1-SW)") (class "Default")
      (node (ref "L4") (pin "1") (pinfunction "1_1") (pintype "bidirectional"))
      (node (ref "U1") (pin "3") (pinfunction "SW_3") (pintype "bidirectional"))
    )
    (net (code "73") (name "Net-(U6-RXD)") (class "Default")
      (node (ref "R71") (pin "2") (pinfunction "2_2") (pintype "passive"))
      (node (ref "U6") (pin "3") (pinfunction "RXD_3") (pintype "bidirectional"))
    )
    (net (code "74") (name "Net-(U6-TXD)") (class "Default")
      (node (ref "R72") (pin "2") (pinfunction "2_2") (pintype "passive"))
      (node (ref "U6") (pin "2") (pinfunction "TXD_2") (pintype "bidirectional"))
    )
    (net (code "75") (name "Net-(U11-VON)") (class "Default")
      (node (ref "C38") (pin "2") (pinfunction "2_2") (pintype "passive"))
      (node (ref "U11") (pin "5") (pinfunction "VON_5") (pintype "bidirectional"))
    )
    (net (code "76") (name "Net-(U11-VOP)") (class "Default")
      (node (ref "C37") (pin "2") (pinfunction "2_2") (pintype "passive"))
      (node (ref "U11") (pin "8") (pinfunction "VOP_8") (pintype "bidirectional"))
    )
    (net (code "77") (name "Net-(U41-CS)") (class "Default")
      (node (ref "R1") (pin "2") (pinfunction "2_2") (pintype "passive"))
      (node (ref "R2") (pin "2") (pinfunction "2_2") (pintype "passive"))
      (node (ref "U41") (pin "15") (pinfunction "CS_15") (pintype "bidirectional"))
    )
    (net (code "78") (name "Net-(U41-VBAT)") (class "Default")
      (node (ref "R41") (pin "2") (pinfunction "2_2") (pintype "passive"))
      (node (ref "U41") (pin "7") (pinfunction "VBAT_7") (pintype "bidirectional"))
    )
    (net (code "79") (name "unconnected-(J3-SBU1-PadA8)") (class "Default")
      (node (ref "J3") (pin "A8") (pinfunction "SBU1_A8") (pintype "bidirectional"))
    )
    (net (code "80") (name "unconnected-(J3-SBU2-PadB8)") (class "Default")
      (node (ref "J3") (pin "B8") (pinfunction "SBU2_B8") (pintype "bidirectional"))
    )
    (net (code "81") (name "unconnected-(JP1-NC-PadP$6)") (class "Default")
      (node (ref "JP1") (pin "P$6") (pinfunction "NC_P$6") (pintype "bidirectional"))
    )
    (net (code "82") (name "unconnected-(SD1-CDN-Pad9)") (class "Default")
      (node (ref "SD1") (pin "9") (pinfunction "CDN_9") (pintype "bidirectional"))
    )
    (net (code "83") (name "unconnected-(U6-CTS#-Pad9)") (class "Default")
      (node (ref "U6") (pin "9") (pinfunction "CTS#_9") (pintype "bidirectional"))
    )
    (net (code "84") (name "unconnected-(U6-DCD#-Pad12)") (class "Default")
      (node (ref "U6") (pin "12") (pinfunction "DCD#_12") (pintype "bidirectional"))
    )
    (net (code "85") (name "unconnected-(U6-DSR#-Pad10)") (class "Default")
      (node (ref "U6") (pin "10") (pinfunction "DSR#_10") (pintype "bidirectional"))
    )
    (net (code "86") (name "unconnected-(U6-DTR#-Pad13)") (class "Default")
      (node (ref "U6") (pin "13") (pinfunction "DTR#_13") (pintype "bidirectional"))
    )
    (net (code "87") (name "unconnected-(U6-RI#-Pad11)") (class "Default")
      (node (ref "U6") (pin "11") (pinfunction "RI#_11") (pintype "bidirectional"))
    )
    (net (code "88") (name "unconnected-(U6-RS232-Pad15)") (class "Default")
      (node (ref "U6") (pin "15") (pinfunction "RS232_15") (pintype "bidirectional"))
    )
    (net (code "89") (name "unconnected-(U6-RTS#-Pad14)") (class "Default")
      (node (ref "U6") (pin "14") (pinfunction "RTS#_14") (pintype "bidirectional"))
    )
    (net (code "90") (name "unconnected-(U6-XI-Pad7)") (class "Default")
      (node (ref "U6") (pin "7") (pinfunction "XI_7") (pintype "bidirectional"))
    )
    (net (code "91") (name "unconnected-(U6-XO-Pad8)") (class "Default")
      (node (ref "U6") (pin "8") (pinfunction "XO_8") (pintype "bidirectional"))
    )
    (net (code "92") (name "unconnected-(U11-PE-Pad9)") (class "Default")
      (node (ref "U11") (pin "9") (pinfunction "PE_9") (pintype "bidirectional"))
    )
    (net (code "93") (name "unconnected-(U41-BUESY-Pad13)") (class "Default")
      (node (ref "U41") (pin "13") (pinfunction "BUESY_13") (pintype "bidirectional"))
    )
    (net (code "94") (name "unconnected-(U41-IN-Pad8)") (class "Default")
      (node (ref "U41") (pin "8") (pinfunction "IN_8") (pintype "bidirectional"))
    )
  )
)
